# Schematic_Sheet_Arduino.net
KiCad netlist of a schematic drawn in Altium Designer
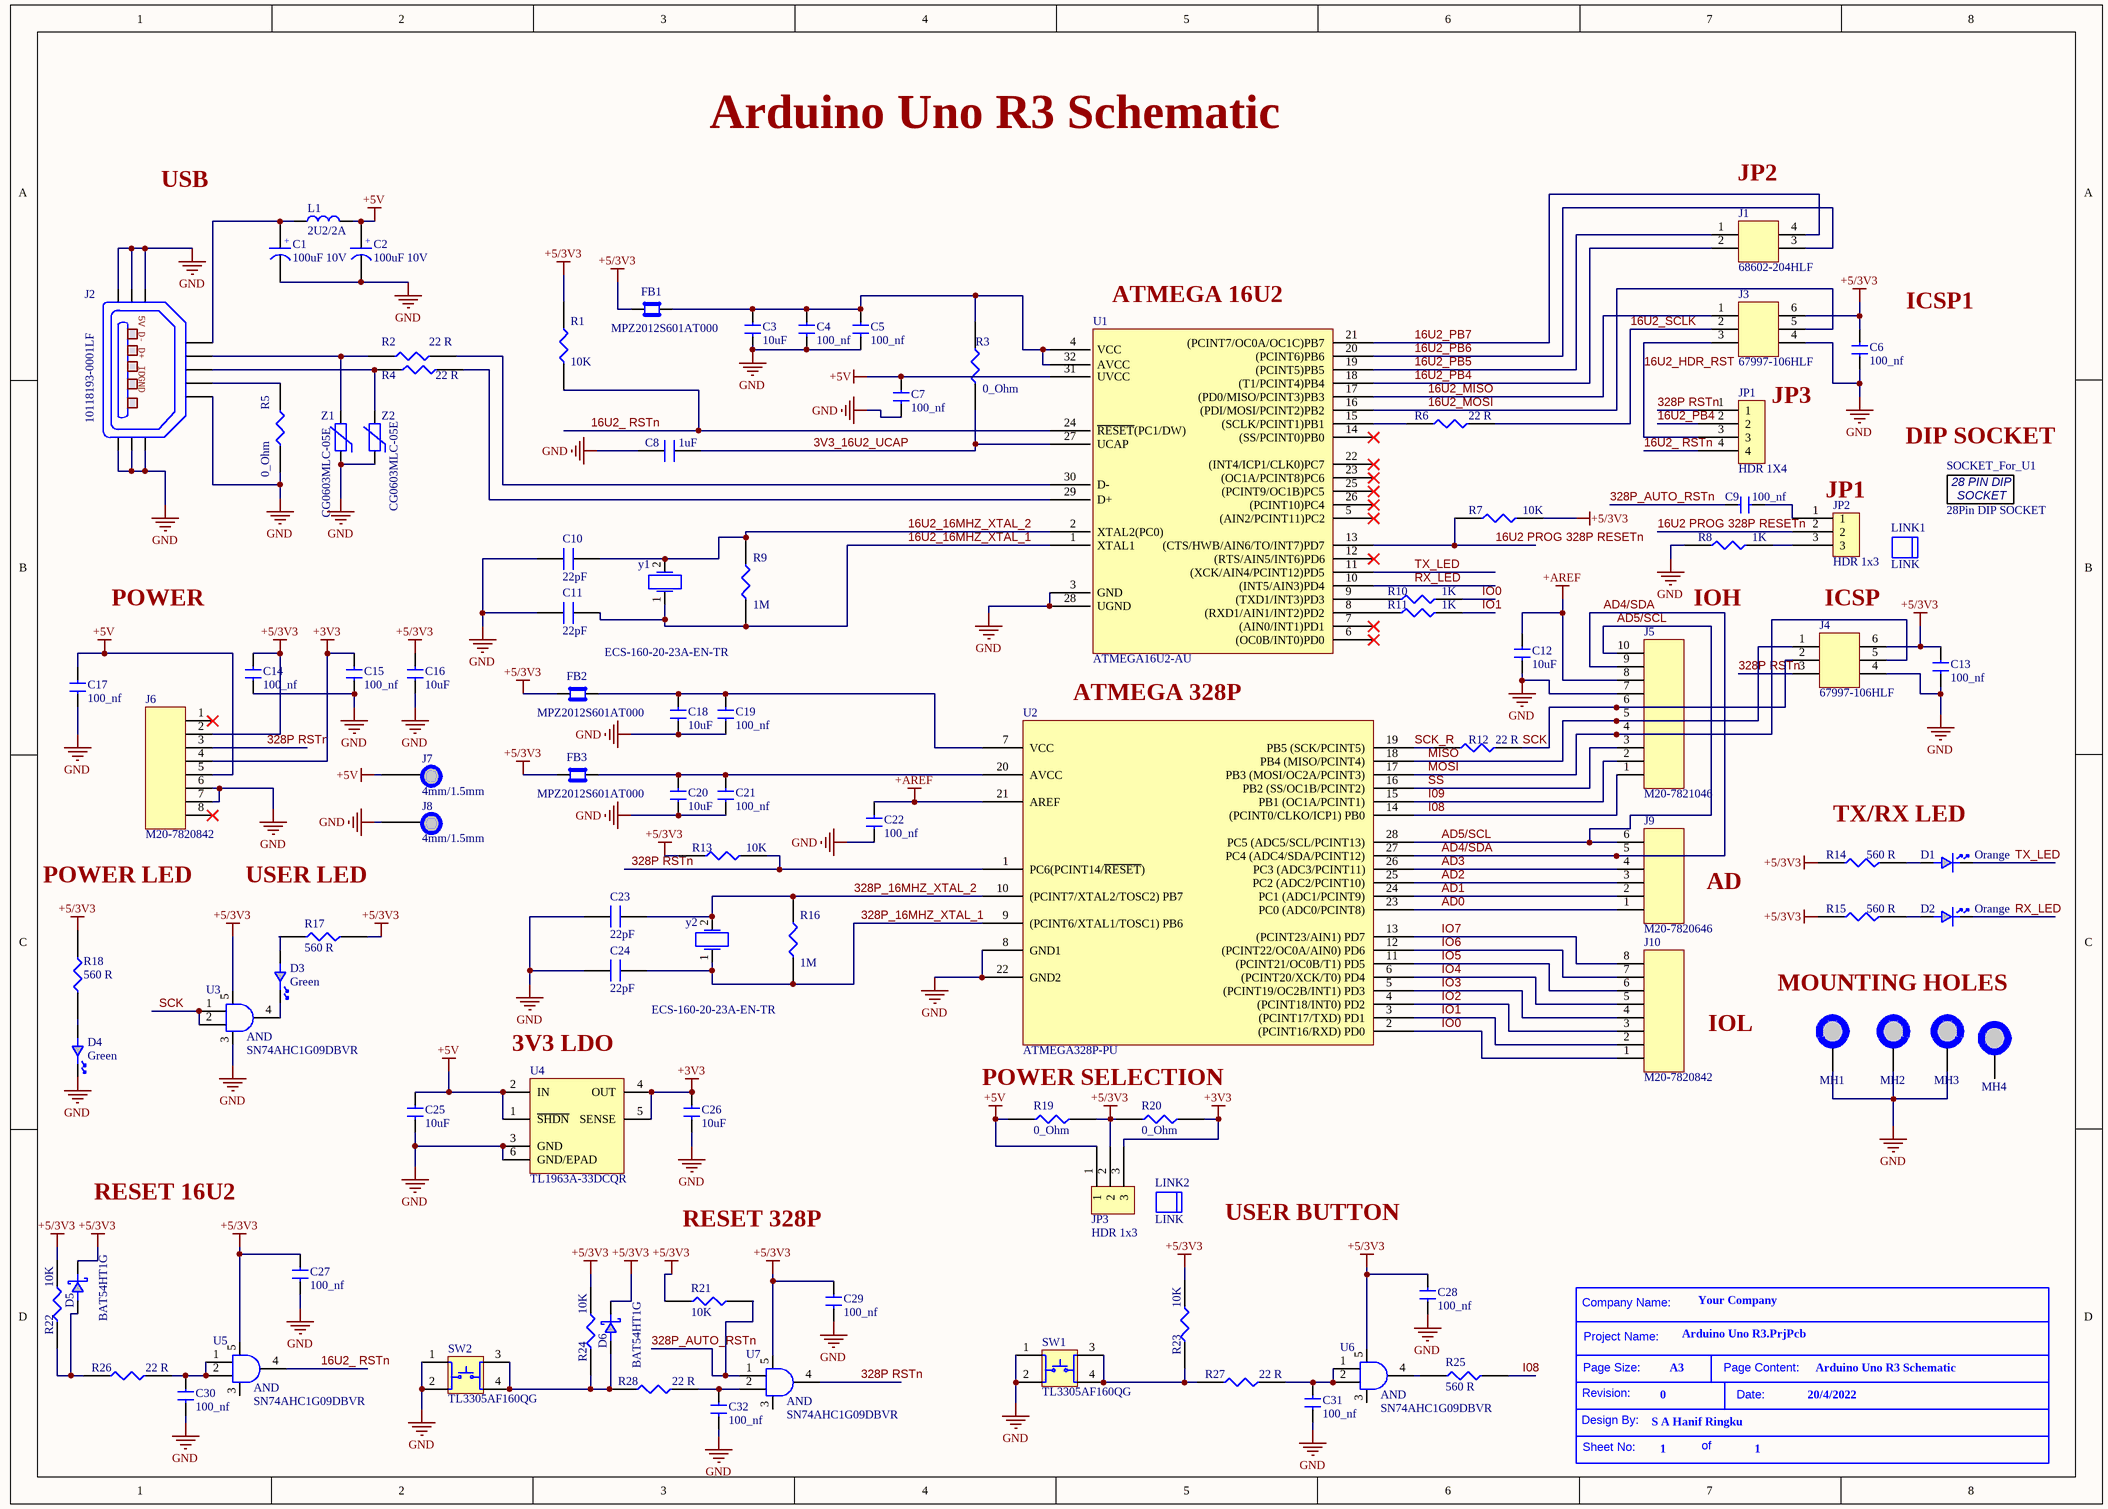
[diagram p0: Schematic Sheet Arduino .SchDoc]

(export (version "E")
  (design (tool "Eeschema 10.0.6"))
  (components
    (comp (ref "*")
      (value "Title_Block")
      (libsource (lib "Component Schematic Library V1") (part "Title_Block"))
    )
    (comp (ref "C1")
      (value "100uF 10V")
      (footprint "Cap_Alu_C_Size")
      (description "贴片铝电解电容 100uF ±20% 10V 1000hrs@85°C AEC_D5.0x5.4mm_SM")
      (fields
        (field (name "MANUFACTURER") "Panasonic")
        (field (name "MANUFACTURER PART NUMBER") "EEE-1AA101WR")
      )
      (libsource (lib "Component Schematic Library V1") (part "CAP_POLAR_100uf_10V"))
    )
    (comp (ref "C2")
      (value "100uF 10V")
      (footprint "Cap_Alu_C_Size")
      (description "贴片铝电解电容 100uF ±20% 10V 1000hrs@85°C AEC_D5.0x5.4mm_SM")
      (fields
        (field (name "MANUFACTURER") "Panasonic")
        (field (name "MANUFACTURER PART NUMBER") "EEE-1AA101WR")
      )
      (libsource (lib "Component Schematic Library V1") (part "CAP_POLAR_100uf_10V"))
    )
    (comp (ref "C3")
      (value "10uF")
      (footprint "CAP_0805")
      (fields
        (field (name "MANUFACTURER") "TDK")
        (field (name "MANUFACTURER PART NUMBER") "C2012X5R1C106M125AC")
        (field (name "TOLERANCE") "20%")
      )
      (libsource (lib "Component Schematic Library V1") (part "CAP_10uF_0805"))
    )
    (comp (ref "C4")
      (value "100_nf")
      (footprint "CAP_0805")
      (description "Cap Ceramic 0.1uF 50V X7R 10% SMD 0805 125°C Blister Plastic T/R")
      (fields
        (field (name "MANUFACTURER") "TDK")
        (field (name "MANUFACTURER PART NUMBER") "C2012X7R1H104K125AE")
      )
      (libsource (lib "Component Schematic Library V1") (part "CAP_ 0.1uf"))
    )
    (comp (ref "C5")
      (value "100_nf")
      (footprint "CAP_0805")
      (description "Cap Ceramic 0.1uF 50V X7R 10% SMD 0805 125°C Blister Plastic T/R")
      (fields
        (field (name "MANUFACTURER") "TDK")
        (field (name "MANUFACTURER PART NUMBER") "C2012X7R1H104K125AE")
      )
      (libsource (lib "Component Schematic Library V1") (part "CAP_ 0.1uf"))
    )
    (comp (ref "C6")
      (value "100_nf")
      (footprint "CAP_0805")
      (description "Cap Ceramic 0.1uF 50V X7R 10% SMD 0805 125°C Blister Plastic T/R")
      (fields
        (field (name "MANUFACTURER") "TDK")
        (field (name "MANUFACTURER PART NUMBER") "C2012X7R1H104K125AE")
      )
      (libsource (lib "Component Schematic Library V1") (part "CAP_ 0.1uf"))
    )
    (comp (ref "C7")
      (value "100_nf")
      (footprint "CAP_0805")
      (description "Cap Ceramic 0.1uF 50V X7R 10% SMD 0805 125°C Blister Plastic T/R")
      (fields
        (field (name "MANUFACTURER") "TDK")
        (field (name "MANUFACTURER PART NUMBER") "C2012X7R1H104K125AE")
      )
      (libsource (lib "Component Schematic Library V1") (part "CAP_ 0.1uf"))
    )
    (comp (ref "C8")
      (value "1uF")
      (footprint "CAP_0805")
      (fields
        (field (name "MANUFACTURER") "TDK")
        (field (name "MANUFACTURER PART NUMBER") "C2012X5R1E105K125AA")
        (field (name "TOLERANCE") "10%")
      )
      (libsource (lib "Component Schematic Library V1") (part "CAP_1uF_0805"))
    )
    (comp (ref "C9")
      (value "100_nf")
      (footprint "CAP_0805")
      (description "Cap Ceramic 0.1uF 50V X7R 10% SMD 0805 125°C Blister Plastic T/R")
      (fields
        (field (name "MANUFACTURER") "TDK")
        (field (name "MANUFACTURER PART NUMBER") "C2012X7R1H104K125AE")
      )
      (libsource (lib "Component Schematic Library V1") (part "CAP_ 0.1uf"))
    )
    (comp (ref "C10")
      (value "22pF")
      (footprint "CAP_0805")
      (description "Cap Ceramic 22pF 50V X7R 5% Pad SMD 0805 125C T/R")
      (fields
        (field (name "MANUFACTURER") "KEMET")
        (field (name "MANUFACTURER PART NUMBER") "C0805C220J5RAC7800")
      )
      (libsource (lib "Component Schematic Library V1") (part "CAP_22pF_0805"))
    )
    (comp (ref "C11")
      (value "22pF")
      (footprint "CAP_0805")
      (description "Cap Ceramic 22pF 50V X7R 5% Pad SMD 0805 125C T/R")
      (fields
        (field (name "MANUFACTURER") "KEMET")
        (field (name "MANUFACTURER PART NUMBER") "C0805C220J5RAC7800")
      )
      (libsource (lib "Component Schematic Library V1") (part "CAP_22pF_0805"))
    )
    (comp (ref "C12")
      (value "10uF")
      (footprint "CAP_0805")
      (fields
        (field (name "MANUFACTURER") "TDK")
        (field (name "MANUFACTURER PART NUMBER") "C2012X5R1C106M125AC")
        (field (name "TOLERANCE") "20%")
      )
      (libsource (lib "Component Schematic Library V1") (part "CAP_10uF_0805"))
    )
    (comp (ref "C13")
      (value "100_nf")
      (footprint "CAP_0805")
      (description "Cap Ceramic 0.1uF 50V X7R 10% SMD 0805 125°C Blister Plastic T/R")
      (fields
        (field (name "MANUFACTURER") "TDK")
        (field (name "MANUFACTURER PART NUMBER") "C2012X7R1H104K125AE")
      )
      (libsource (lib "Component Schematic Library V1") (part "CAP_ 0.1uf"))
    )
    (comp (ref "C14")
      (value "100_nf")
      (footprint "CAP_0805")
      (description "Cap Ceramic 0.1uF 50V X7R 10% SMD 0805 125°C Blister Plastic T/R")
      (fields
        (field (name "MANUFACTURER") "TDK")
        (field (name "MANUFACTURER PART NUMBER") "C2012X7R1H104K125AE")
      )
      (libsource (lib "Component Schematic Library V1") (part "CAP_ 0.1uf"))
    )
    (comp (ref "C15")
      (value "100_nf")
      (footprint "CAP_0805")
      (description "Cap Ceramic 0.1uF 50V X7R 10% SMD 0805 125°C Blister Plastic T/R")
      (fields
        (field (name "MANUFACTURER") "TDK")
        (field (name "MANUFACTURER PART NUMBER") "C2012X7R1H104K125AE")
      )
      (libsource (lib "Component Schematic Library V1") (part "CAP_ 0.1uf"))
    )
    (comp (ref "C16")
      (value "10uF")
      (footprint "CAP_0805")
      (fields
        (field (name "MANUFACTURER") "TDK")
        (field (name "MANUFACTURER PART NUMBER") "C2012X5R1C106M125AC")
        (field (name "TOLERANCE") "20%")
      )
      (libsource (lib "Component Schematic Library V1") (part "CAP_10uF_0805"))
    )
    (comp (ref "C17")
      (value "100_nf")
      (footprint "CAP_0805")
      (description "Cap Ceramic 0.1uF 50V X7R 10% SMD 0805 125°C Blister Plastic T/R")
      (fields
        (field (name "MANUFACTURER") "TDK")
        (field (name "MANUFACTURER PART NUMBER") "C2012X7R1H104K125AE")
      )
      (libsource (lib "Component Schematic Library V1") (part "CAP_ 0.1uf"))
    )
    (comp (ref "C18")
      (value "10uF")
      (footprint "CAP_0805")
      (fields
        (field (name "MANUFACTURER") "TDK")
        (field (name "MANUFACTURER PART NUMBER") "C2012X5R1C106M125AC")
        (field (name "TOLERANCE") "20%")
      )
      (libsource (lib "Component Schematic Library V1") (part "CAP_10uF_0805"))
    )
    (comp (ref "C19")
      (value "100_nf")
      (footprint "CAP_0805")
      (description "Cap Ceramic 0.1uF 50V X7R 10% SMD 0805 125°C Blister Plastic T/R")
      (fields
        (field (name "MANUFACTURER") "TDK")
        (field (name "MANUFACTURER PART NUMBER") "C2012X7R1H104K125AE")
      )
      (libsource (lib "Component Schematic Library V1") (part "CAP_ 0.1uf"))
    )
    (comp (ref "C20")
      (value "10uF")
      (footprint "CAP_0805")
      (fields
        (field (name "MANUFACTURER") "TDK")
        (field (name "MANUFACTURER PART NUMBER") "C2012X5R1C106M125AC")
        (field (name "TOLERANCE") "20%")
      )
      (libsource (lib "Component Schematic Library V1") (part "CAP_10uF_0805"))
    )
    (comp (ref "C21")
      (value "100_nf")
      (footprint "CAP_0805")
      (description "Cap Ceramic 0.1uF 50V X7R 10% SMD 0805 125°C Blister Plastic T/R")
      (fields
        (field (name "MANUFACTURER") "TDK")
        (field (name "MANUFACTURER PART NUMBER") "C2012X7R1H104K125AE")
      )
      (libsource (lib "Component Schematic Library V1") (part "CAP_ 0.1uf"))
    )
    (comp (ref "C22")
      (value "100_nf")
      (footprint "CAP_0805")
      (description "Cap Ceramic 0.1uF 50V X7R 10% SMD 0805 125°C Blister Plastic T/R")
      (fields
        (field (name "MANUFACTURER") "TDK")
        (field (name "MANUFACTURER PART NUMBER") "C2012X7R1H104K125AE")
      )
      (libsource (lib "Component Schematic Library V1") (part "CAP_ 0.1uf"))
    )
    (comp (ref "C23")
      (value "22pF")
      (footprint "CAP_0805")
      (description "Cap Ceramic 22pF 50V X7R 5% Pad SMD 0805 125C T/R")
      (fields
        (field (name "MANUFACTURER") "KEMET")
        (field (name "MANUFACTURER PART NUMBER") "C0805C220J5RAC7800")
      )
      (libsource (lib "Component Schematic Library V1") (part "CAP_22pF_0805"))
    )
    (comp (ref "C24")
      (value "22pF")
      (footprint "CAP_0805")
      (description "Cap Ceramic 22pF 50V X7R 5% Pad SMD 0805 125C T/R")
      (fields
        (field (name "MANUFACTURER") "KEMET")
        (field (name "MANUFACTURER PART NUMBER") "C0805C220J5RAC7800")
      )
      (libsource (lib "Component Schematic Library V1") (part "CAP_22pF_0805"))
    )
    (comp (ref "C25")
      (value "10uF")
      (footprint "CAP_0805")
      (fields
        (field (name "MANUFACTURER") "TDK")
        (field (name "MANUFACTURER PART NUMBER") "C2012X5R1C106M125AC")
        (field (name "TOLERANCE") "20%")
      )
      (libsource (lib "Component Schematic Library V1") (part "CAP_10uF_0805"))
    )
    (comp (ref "C26")
      (value "10uF")
      (footprint "CAP_0805")
      (fields
        (field (name "MANUFACTURER") "TDK")
        (field (name "MANUFACTURER PART NUMBER") "C2012X5R1C106M125AC")
        (field (name "TOLERANCE") "20%")
      )
      (libsource (lib "Component Schematic Library V1") (part "CAP_10uF_0805"))
    )
    (comp (ref "C27")
      (value "100_nf")
      (footprint "CAP_0805")
      (description "Cap Ceramic 0.1uF 50V X7R 10% SMD 0805 125°C Blister Plastic T/R")
      (fields
        (field (name "MANUFACTURER") "TDK")
        (field (name "MANUFACTURER PART NUMBER") "C2012X7R1H104K125AE")
      )
      (libsource (lib "Component Schematic Library V1") (part "CAP_ 0.1uf"))
    )
    (comp (ref "C28")
      (value "100_nf")
      (footprint "CAP_0805")
      (description "Cap Ceramic 0.1uF 50V X7R 10% SMD 0805 125°C Blister Plastic T/R")
      (fields
        (field (name "MANUFACTURER") "TDK")
        (field (name "MANUFACTURER PART NUMBER") "C2012X7R1H104K125AE")
      )
      (libsource (lib "Component Schematic Library V1") (part "CAP_ 0.1uf"))
    )
    (comp (ref "C29")
      (value "100_nf")
      (footprint "CAP_0805")
      (description "Cap Ceramic 0.1uF 50V X7R 10% SMD 0805 125°C Blister Plastic T/R")
      (fields
        (field (name "MANUFACTURER") "TDK")
        (field (name "MANUFACTURER PART NUMBER") "C2012X7R1H104K125AE")
      )
      (libsource (lib "Component Schematic Library V1") (part "CAP_ 0.1uf"))
    )
    (comp (ref "C30")
      (value "100_nf")
      (footprint "CAP_0805")
      (description "Cap Ceramic 0.1uF 50V X7R 10% SMD 0805 125°C Blister Plastic T/R")
      (fields
        (field (name "MANUFACTURER") "TDK")
        (field (name "MANUFACTURER PART NUMBER") "C2012X7R1H104K125AE")
      )
      (libsource (lib "Component Schematic Library V1") (part "CAP_ 0.1uf"))
    )
    (comp (ref "C31")
      (value "100_nf")
      (footprint "CAP_0805")
      (description "Cap Ceramic 0.1uF 50V X7R 10% SMD 0805 125°C Blister Plastic T/R")
      (fields
        (field (name "MANUFACTURER") "TDK")
        (field (name "MANUFACTURER PART NUMBER") "C2012X7R1H104K125AE")
      )
      (libsource (lib "Component Schematic Library V1") (part "CAP_ 0.1uf"))
    )
    (comp (ref "C32")
      (value "100_nf")
      (footprint "CAP_0805")
      (description "Cap Ceramic 0.1uF 50V X7R 10% SMD 0805 125°C Blister Plastic T/R")
      (fields
        (field (name "MANUFACTURER") "TDK")
        (field (name "MANUFACTURER PART NUMBER") "C2012X7R1H104K125AE")
      )
      (libsource (lib "Component Schematic Library V1") (part "CAP_ 0.1uf"))
    )
    (comp (ref "D1")
      (value "Orange")
      (footprint "LED 0603")
      (description "Smartled Orange Lc")
      (fields
        (field (name "MANUFACTURER") "Osram Opto")
        (field (name "MANUFACTURER PART NUMBER") "LOL29K-H2K1-24-Z")
      )
      (libsource (lib "Component Schematic Library V1") (part "LED_Orange"))
    )
    (comp (ref "D2")
      (value "Orange")
      (footprint "LED 0603")
      (description "Smartled Orange Lc")
      (fields
        (field (name "MANUFACTURER") "Osram Opto")
        (field (name "MANUFACTURER PART NUMBER") "LOL29K-H2K1-24-Z")
      )
      (libsource (lib "Component Schematic Library V1") (part "LED_Orange"))
    )
    (comp (ref "D3")
      (value "Green")
      (footprint "LED 0603")
      (description "LED Single Chip Green 570nm 20mA 2-Pin 0603 T/R")
      (fields
        (field (name "MANUFACTURER") "Osram Opto")
        (field (name "MANUFACTURER PART NUMBER") "LGL29K-G2J1-24-Z")
      )
      (libsource (lib "Component Schematic Library V1") (part "LED_Green"))
    )
    (comp (ref "D4")
      (value "Green")
      (footprint "LED 0603")
      (description "LED Single Chip Green 570nm 20mA 2-Pin 0603 T/R")
      (fields
        (field (name "MANUFACTURER") "Osram Opto")
        (field (name "MANUFACTURER PART NUMBER") "LGL29K-G2J1-24-Z")
      )
      (libsource (lib "Component Schematic Library V1") (part "LED_Green"))
    )
    (comp (ref "D5")
      (value "BAT54HT1G")
      (footprint "SOD323")
      (description "VR=30V IF=200mA 10pF P=200mW")
      (fields (field (name "MANUFACTURER") "ON Semiconductor / Fairchild"))
      (libsource (lib "Component Schematic Library V1") (part "Shottky_Diode"))
    )
    (comp (ref "D6")
      (value "BAT54HT1G")
      (footprint "SOD323")
      (description "VR=30V IF=200mA 10pF P=200mW")
      (fields (field (name "MANUFACTURER") "ON Semiconductor / Fairchild"))
      (libsource (lib "Component Schematic Library V1") (part "Shottky_Diode"))
    )
    (comp (ref "FB1")
      (value "MPZ2012S601AT000")
      (footprint "CAP_0805")
      (description "0805 600Ω ±25% DCR=0.1Ω 2A")
      (fields (field (name "MANUFACTURER") "TDK"))
      (libsource (lib "Component Schematic Library V1") (part "Ferrite Bit"))
    )
    (comp (ref "FB2")
      (value "MPZ2012S601AT000")
      (footprint "CAP_0805")
      (description "0805 600Ω ±25% DCR=0.1Ω 2A")
      (fields (field (name "MANUFACTURER") "TDK"))
      (libsource (lib "Component Schematic Library V1") (part "Ferrite Bit"))
    )
    (comp (ref "FB3")
      (value "MPZ2012S601AT000")
      (footprint "CAP_0805")
      (description "0805 600Ω ±25% DCR=0.1Ω 2A")
      (fields (field (name "MANUFACTURER") "TDK"))
      (libsource (lib "Component Schematic Library V1") (part "Ferrite Bit"))
    )
    (comp (ref "J1")
      (value "68602-204HLF")
      (footprint "Male_HDR_2X2_2.54")
      (description "Conn Unshrouded Header HDR 4 POS 2.54mm Solder ST Top Entry Thru-Hole BergStik® Bulk")
      (fields (field (name "MANUFACTURER") "Amphenol ICC / FCI"))
      (libsource (lib "Component Schematic Library V1") (part "Male_HDR_2X2_2.54mm_Pitch"))
    )
    (comp (ref "J2")
      (value "10118193-0001LF")
      (footprint "USB")
      (description "FCI Right Angle Surface Mount Mount Female USB Connector; 100 V ac; 1.8A")
      (fields (field (name "MANUFACTURER") "Amphenol ICC / FCI"))
      (libsource (lib "Component Schematic Library V1") (part "Micro_USB"))
    )
    (comp (ref "J3")
      (value "67997-106HLF")
      (footprint "MALE_HDR_3X2_2.54mm")
      (description "Conn Unshrouded Header HDR 6 POS 2.54mm Solder ST Top Entry Thru-Hole BergStik® Bulk")
      (fields (field (name "MANUFACTURER") "Amphenol ICC / FCI"))
      (libsource (lib "Component Schematic Library V1") (part "Male_HDR_3X2_2.54mm_Pitch"))
    )
    (comp (ref "J4")
      (value "67997-106HLF")
      (footprint "MALE_HDR_3X2_2.54mm")
      (description "Conn Unshrouded Header HDR 6 POS 2.54mm Solder ST Top Entry Thru-Hole BergStik® Bulk")
      (fields (field (name "MANUFACTURER") "Amphenol ICC / FCI"))
      (libsource (lib "Component Schematic Library V1") (part "Male_HDR_3X2_2.54mm_Pitch"))
    )
    (comp (ref "J5")
      (value "M20-7821046")
      (footprint "Female_HDR_10\\X1_2.54mm_Pitch")
      (description "2.54mm (0.1\") Pitch SIL Vertical PC Tail Socket Assembly, tin, 10 contacts")
      (fields (field (name "MANUFACTURER") "Harwin"))
      (libsource (lib "Component Schematic Library V1") (part "Female_Header 10X1_Pins_2.54_mm_Pitch"))
    )
    (comp (ref "J6")
      (value "M20-7820842")
      (footprint "Female_HDR_8\\X1_2.54mm_Pitch")
      (description "2.54mm (0.1\") Pitch SIL Vertical PC Tail Socket Assembly, selective gold + tin, 8 contacts")
      (fields (field (name "MANUFACTURER") "Harwin"))
      (libsource (lib "") (part "Female_Header 8X1_Pins_2.54_mm_Pitch_1"))
    )
    (comp (ref "J7")
      (value "4mm/1.5mm")
      (footprint "PAD_WITH_HOLE_4MM/1.5MM")
      (description "PAD With Whole 4mm/1.5mm")
      (libsource (lib "Component Schematic Library V1") (part "PAD_WITH_HOLE_4mm_5mm"))
    )
    (comp (ref "J8")
      (value "4mm/1.5mm")
      (footprint "PAD_WITH_HOLE_4MM/1.5MM")
      (description "PAD With Whole 4mm/1.5mm")
      (libsource (lib "Component Schematic Library V1") (part "PAD_WITH_HOLE_4mm_5mm"))
    )
    (comp (ref "J9")
      (value "M20-7820646")
      (footprint "Female_HDR_6X1_2.54mm_Pitch")
      (description "2.54mm (0.1\") Pitch SIL Vertical PC Tail Socket Assembly, tin, 6 contacts")
      (fields (field (name "MANUFACTURER") "Harwin"))
      (libsource (lib "Component Schematic Library V1") (part "Female_Header 6X1_Pins_2.54_mm_Pitch"))
    )
    (comp (ref "J10")
      (value "M20-7820842")
      (footprint "Female_HDR_8\\X1_2.54mm_Pitch")
      (description "2.54mm (0.1\") Pitch SIL Vertical PC Tail Socket Assembly, selective gold + tin, 8 contacts")
      (fields (field (name "MANUFACTURER") "Harwin"))
      (libsource (lib "Component Schematic Library V1") (part "Female_Header 8X1_Pins_2.54_mm_Pitch"))
    )
    (comp (ref "JP1")
      (value "HDR 1X4")
      (footprint "HDR 1X4")
      (description "Conn Unshrouded Header HDR 4 POS 2.54mm Solder ST Thru-Hole Bag")
      (fields
        (field (name "MANUFACTURER") "Amphenol ICC")
        (field (name "MANUFACTURER PART NUMBER") "68001-204HLF")
      )
      (libsource (lib "Component Schematic Library V1") (part "MALE_HDR_4X1_Unschrouded"))
    )
    (comp (ref "JP2")
      (value "HDR 1x3")
      (footprint "HDR 1x3")
      (description "Conn Unshrouded Header HDR 3 POS 2.54mm Solder ST Top Entry Thru-Hole BergStik® Bulk")
      (fields
        (field (name "MANUFACTURER") "Amphenol ICC / FCI")
        (field (name "MANUFACTURER PART NUMBER") "68797-403HLF")
      )
      (libsource (lib "Component Schematic Library V1") (part "Male_HDR_1X3_Unschrouded"))
    )
    (comp (ref "JP3")
      (value "HDR 1x3")
      (footprint "HDR 1x3")
      (description "Conn Unshrouded Header HDR 3 POS 2.54mm Solder ST Top Entry Thru-Hole BergStik® Bulk")
      (fields
        (field (name "MANUFACTURER") "Amphenol ICC / FCI")
        (field (name "MANUFACTURER PART NUMBER") "68797-403HLF")
      )
      (libsource (lib "") (part "Male_HDR_1X3_Unschrouded_1"))
    )
    (comp (ref "L1")
      (value "2U2/2A")
      (footprint "C1210_Inductor")
      (description "Inductor RF Chip Wirewound 2.2uH 20% 100KHz 1.13A 0.104Ohm DCR 1210 T/R")
      (fields
        (field (name "MANUFACTURER") "KEMET")
        (field (name "MANUFACTURER PART NUMBER") "L1210R2R2MDWIT")
      )
      (libsource (lib "Component Schematic Library V1") (part "Inductor_2.2uH"))
    )
    (comp (ref "LINK1")
      (value "LINK")
      (description "2 Position 2.54 mm Centerline Single Circuit Open Top Jumper")
      (fields
        (field (name "MANUFACTURER") "Sullins")
        (field (name "MANUFACTURER PART NUMBER") "QPC02SXGN-RC")
      )
      (libsource (lib "Component Schematic Library V1") (part "Connector_Open_Top_Jumper"))
    )
    (comp (ref "LINK2")
      (value "LINK")
      (description "2 Position 2.54 mm Centerline Single Circuit Open Top Jumper")
      (fields
        (field (name "MANUFACTURER") "Sullins")
        (field (name "MANUFACTURER PART NUMBER") "QPC02SXGN-RC")
      )
      (libsource (lib "Component Schematic Library V1") (part "Connector_Open_Top_Jumper"))
    )
    (comp (ref "MH1")
      (value "MH_7.4_MHC_3.2")
      (footprint "MH_7.4 and 3.2 mm")
      (description "Mounting Hole 7.4 mm Diameter and 3.2 mm drill")
      (libsource (lib "Component Schematic Library V1") (part "MH 7.4 /3.2"))
    )
    (comp (ref "MH2")
      (value "MH_7.4_MHC_3.2")
      (footprint "MH_7.4 and 3.2 mm")
      (description "Mounting Hole 7.4 mm Diameter and 3.2 mm drill")
      (libsource (lib "Component Schematic Library V1") (part "MH 7.4 /3.2"))
    )
    (comp (ref "MH3")
      (value "MH_7.4_MHC_3.2")
      (footprint "MH_7.4 and 3.2 mm")
      (description "Mounting Hole 7.4 mm Diameter and 3.2 mm drill")
      (libsource (lib "Component Schematic Library V1") (part "MH 7.4 /3.2"))
    )
    (comp (ref "MH4")
      (value "Mountain Hole Non Plated")
      (footprint "MH_non_plated")
      (description "Mountain Hole 7.4 mm diameter no coper drill 3.2 mm")
      (libsource (lib "Component Schematic Library V1") (part "MH Non Plated 7.4X3.2"))
    )
    (comp (ref "R1")
      (value "10K")
      (footprint "R_0805")
      (description "贴片电阻 10000Ω ± 1.00% 0.125W ± 100ppm/℃ 0805")
      (fields
        (field (name "MANUFACTURER") "Yageo")
        (field (name "MANUFACTURER PART NUMBER") "RC0805FR-0710KL")
      )
      (libsource (lib "Component Schematic Library V1") (part "RES_10_K_0805"))
    )
    (comp (ref "R2")
      (value "22 R")
      (footprint "R_0805")
      (description "贴片电阻 22Ω ± 1.00% 0.125W ± 100ppm/℃ 0805")
      (fields
        (field (name "MANUFACTURER") "Yageo")
        (field (name "MANUFACTURER PART NUMBER") "RC0805FR-0722RL")
      )
      (libsource (lib "Component Schematic Library V1") (part "RES_22_Ohm_0805"))
    )
    (comp (ref "R3")
      (value "0_Ohm")
      (footprint "R_0805")
      (description "贴片电阻 0Ω ±5% 1/8W 0805")
      (fields
        (field (name "MANUFACTURER") "Yageo")
        (field (name "MANUFACTURER PART NUMBER") "RC0805JR-070RL")
      )
      (libsource (lib "Component Schematic Library V1") (part "RES_0_Ohm_0805"))
    )
    (comp (ref "R4")
      (value "22 R")
      (footprint "R_0805")
      (description "贴片电阻 22Ω ± 1.00% 0.125W ± 100ppm/℃ 0805")
      (fields
        (field (name "MANUFACTURER") "Yageo")
        (field (name "MANUFACTURER PART NUMBER") "RC0805FR-0722RL")
      )
      (libsource (lib "Component Schematic Library V1") (part "RES_22_Ohm_0805"))
    )
    (comp (ref "R5")
      (value "0_Ohm")
      (footprint "R_0805")
      (description "贴片电阻 0Ω ±5% 1/8W 0805")
      (fields
        (field (name "MANUFACTURER") "Yageo")
        (field (name "MANUFACTURER PART NUMBER") "RC0805JR-070RL")
      )
      (libsource (lib "Component Schematic Library V1") (part "RES_0_Ohm_0805"))
    )
    (comp (ref "R6")
      (value "22 R")
      (footprint "R_0805")
      (description "贴片电阻 22Ω ± 1.00% 0.125W ± 100ppm/℃ 0805")
      (fields
        (field (name "MANUFACTURER") "Yageo")
        (field (name "MANUFACTURER PART NUMBER") "RC0805FR-0722RL")
      )
      (libsource (lib "Component Schematic Library V1") (part "RES_22_Ohm_0805"))
    )
    (comp (ref "R7")
      (value "10K")
      (footprint "R_0805")
      (description "贴片电阻 10000Ω ± 1.00% 0.125W ± 100ppm/℃ 0805")
      (fields
        (field (name "MANUFACTURER") "Yageo")
        (field (name "MANUFACTURER PART NUMBER") "RC0805FR-0710KL")
      )
      (libsource (lib "Component Schematic Library V1") (part "RES_10_K_0805"))
    )
    (comp (ref "R8")
      (value "1K")
      (footprint "R_0805")
      (description "贴片电阻 1000Ω ± 1.00% 0.125W ± 100ppm/℃ 0805")
      (fields
        (field (name "MANUFACTURER") "Yageo")
        (field (name "MANUFACTURER PART NUMBER") "RC0805FR-071KL")
      )
      (libsource (lib "Component Schematic Library V1") (part "RES_1_K_0805"))
    )
    (comp (ref "R9")
      (value "1M")
      (footprint "R_0805")
      (description "贴片电阻 1000000Ω ± 1.00% 0.125W ± 100ppm/℃ 0805")
      (fields
        (field (name "MANUFACTURER") "Yageo")
        (field (name "MANUFACTURER PART NUMBER") "RC0805FR-071ML")
      )
      (libsource (lib "Component Schematic Library V1") (part "RES_1M_0805"))
    )
    (comp (ref "R10")
      (value "1K")
      (footprint "R_0805")
      (description "贴片电阻 1000Ω ± 1.00% 0.125W ± 100ppm/℃ 0805")
      (fields
        (field (name "MANUFACTURER") "Yageo")
        (field (name "MANUFACTURER PART NUMBER") "RC0805FR-071KL")
      )
      (libsource (lib "Component Schematic Library V1") (part "RES_1_K_0805"))
    )
    (comp (ref "R11")
      (value "1K")
      (footprint "R_0805")
      (description "贴片电阻 1000Ω ± 1.00% 0.125W ± 100ppm/℃ 0805")
      (fields
        (field (name "MANUFACTURER") "Yageo")
        (field (name "MANUFACTURER PART NUMBER") "RC0805FR-071KL")
      )
      (libsource (lib "Component Schematic Library V1") (part "RES_1_K_0805"))
    )
    (comp (ref "R12")
      (value "22 R")
      (footprint "R_0805")
      (description "贴片电阻 22Ω ± 1.00% 0.125W ± 100ppm/℃ 0805")
      (fields
        (field (name "MANUFACTURER") "Yageo")
        (field (name "MANUFACTURER PART NUMBER") "RC0805FR-0722RL")
      )
      (libsource (lib "Component Schematic Library V1") (part "RES_22_Ohm_0805"))
    )
    (comp (ref "R13")
      (value "10K")
      (footprint "R_0805")
      (description "贴片电阻 10000Ω ± 1.00% 0.125W ± 100ppm/℃ 0805")
      (fields
        (field (name "MANUFACTURER") "Yageo")
        (field (name "MANUFACTURER PART NUMBER") "RC0805FR-0710KL")
      )
      (libsource (lib "Component Schematic Library V1") (part "RES_10_K_0805"))
    )
    (comp (ref "R14")
      (value "560 R")
      (footprint "R_0805")
      (description "贴片电阻 560Ω ± 1.00% 0.125W ± 100ppm/℃ 0805")
      (fields
        (field (name "MANUFACTURER") "Yageo")
        (field (name "MANUFACTURER PART NUMBER") "RC0805FR-07560RL")
      )
      (libsource (lib "Component Schematic Library V1") (part "RES_560_Ohm_0805"))
    )
    (comp (ref "R15")
      (value "560 R")
      (footprint "R_0805")
      (description "贴片电阻 560Ω ± 1.00% 0.125W ± 100ppm/℃ 0805")
      (fields
        (field (name "MANUFACTURER") "Yageo")
        (field (name "MANUFACTURER PART NUMBER") "RC0805FR-07560RL")
      )
      (libsource (lib "Component Schematic Library V1") (part "RES_560_Ohm_0805"))
    )
    (comp (ref "R16")
      (value "1M")
      (footprint "R_0805")
      (description "贴片电阻 1000000Ω ± 1.00% 0.125W ± 100ppm/℃ 0805")
      (fields
        (field (name "MANUFACTURER") "Yageo")
        (field (name "MANUFACTURER PART NUMBER") "RC0805FR-071ML")
      )
      (libsource (lib "Component Schematic Library V1") (part "RES_1M_0805"))
    )
    (comp (ref "R17")
      (value "560 R")
      (footprint "R_0805")
      (description "贴片电阻 560Ω ± 1.00% 0.125W ± 100ppm/℃ 0805")
      (fields
        (field (name "MANUFACTURER") "Yageo")
        (field (name "MANUFACTURER PART NUMBER") "RC0805FR-07560RL")
      )
      (libsource (lib "Component Schematic Library V1") (part "RES_560_Ohm_0805"))
    )
    (comp (ref "R18")
      (value "560 R")
      (footprint "R_0805")
      (description "贴片电阻 560Ω ± 1.00% 0.125W ± 100ppm/℃ 0805")
      (fields
        (field (name "MANUFACTURER") "Yageo")
        (field (name "MANUFACTURER PART NUMBER") "RC0805FR-07560RL")
      )
      (libsource (lib "Component Schematic Library V1") (part "RES_560_Ohm_0805"))
    )
    (comp (ref "R19")
      (value "0_Ohm")
      (footprint "R_0805")
      (description "贴片电阻 0Ω ±5% 1/8W 0805")
      (fields
        (field (name "MANUFACTURER") "Yageo")
        (field (name "MANUFACTURER PART NUMBER") "RC0805JR-070RL")
      )
      (libsource (lib "Component Schematic Library V1") (part "RES_0_Ohm_0805"))
    )
    (comp (ref "R20")
      (value "0_Ohm")
      (footprint "R_0805")
      (description "贴片电阻 0Ω ±5% 1/8W 0805")
      (fields
        (field (name "MANUFACTURER") "Yageo")
        (field (name "MANUFACTURER PART NUMBER") "RC0805JR-070RL")
      )
      (libsource (lib "Component Schematic Library V1") (part "RES_0_Ohm_0805"))
    )
    (comp (ref "R21")
      (value "10K")
      (footprint "R_0805")
      (description "贴片电阻 10000Ω ± 1.00% 0.125W ± 100ppm/℃ 0805")
      (fields
        (field (name "MANUFACTURER") "Yageo")
        (field (name "MANUFACTURER PART NUMBER") "RC0805FR-0710KL")
      )
      (libsource (lib "Component Schematic Library V1") (part "RES_10_K_0805"))
    )
    (comp (ref "R22")
      (value "10K")
      (footprint "R_0805")
      (description "贴片电阻 10000Ω ± 1.00% 0.125W ± 100ppm/℃ 0805")
      (fields
        (field (name "MANUFACTURER") "Yageo")
        (field (name "MANUFACTURER PART NUMBER") "RC0805FR-0710KL")
      )
      (libsource (lib "Component Schematic Library V1") (part "RES_10_K_0805"))
    )
    (comp (ref "R23")
      (value "10K")
      (footprint "R_0805")
      (description "贴片电阻 10000Ω ± 1.00% 0.125W ± 100ppm/℃ 0805")
      (fields
        (field (name "MANUFACTURER") "Yageo")
        (field (name "MANUFACTURER PART NUMBER") "RC0805FR-0710KL")
      )
      (libsource (lib "Component Schematic Library V1") (part "RES_10_K_0805"))
    )
    (comp (ref "R24")
      (value "10K")
      (footprint "R_0805")
      (description "贴片电阻 10000Ω ± 1.00% 0.125W ± 100ppm/℃ 0805")
      (fields
        (field (name "MANUFACTURER") "Yageo")
        (field (name "MANUFACTURER PART NUMBER") "RC0805FR-0710KL")
      )
      (libsource (lib "Component Schematic Library V1") (part "RES_10_K_0805"))
    )
    (comp (ref "R25")
      (value "560 R")
      (footprint "R_0805")
      (description "贴片电阻 560Ω ± 1.00% 0.125W ± 100ppm/℃ 0805")
      (fields
        (field (name "MANUFACTURER") "Yageo")
        (field (name "MANUFACTURER PART NUMBER") "RC0805FR-07560RL")
      )
      (libsource (lib "Component Schematic Library V1") (part "RES_560_Ohm_0805"))
    )
    (comp (ref "R26")
      (value "22 R")
      (footprint "R_0805")
      (description "贴片电阻 22Ω ± 1.00% 0.125W ± 100ppm/℃ 0805")
      (fields
        (field (name "MANUFACTURER") "Yageo")
        (field (name "MANUFACTURER PART NUMBER") "RC0805FR-0722RL")
      )
      (libsource (lib "Component Schematic Library V1") (part "RES_22_Ohm_0805"))
    )
    (comp (ref "R27")
      (value "22 R")
      (footprint "R_0805")
      (description "贴片电阻 22Ω ± 1.00% 0.125W ± 100ppm/℃ 0805")
      (fields
        (field (name "MANUFACTURER") "Yageo")
        (field (name "MANUFACTURER PART NUMBER") "RC0805FR-0722RL")
      )
      (libsource (lib "Component Schematic Library V1") (part "RES_22_Ohm_0805"))
    )
    (comp (ref "R28")
      (value "22 R")
      (footprint "R_0805")
      (description "贴片电阻 22Ω ± 1.00% 0.125W ± 100ppm/℃ 0805")
      (fields
        (field (name "MANUFACTURER") "Yageo")
        (field (name "MANUFACTURER PART NUMBER") "RC0805FR-0722RL")
      )
      (libsource (lib "Component Schematic Library V1") (part "RES_22_Ohm_0805"))
    )
    (comp (ref "SOCKET_For_U1")
      (value "28Pin DIP SOCKET")
      (footprint "28 DIP_7.62mm_SOCKET")
      (description "Socket DIP 28Cnts DualWipe 0.3InSpc. PhosphorBronze Nickel KinkedTail 4800Series")
      (fields (field (name "MANUFACTURER") "3M") (field (name "MANUFACTURER PART NUMBER") "4828-3004-CP"))
      (libsource (lib "Component Schematic Library V1") (part "28_PIN_DIP_Socket"))
    )
    (comp (ref "SW1")
      (value "TL3305AF160QG")
      (footprint "SW_PB_SMD")
      (description "TL3305A Series SPST 12 V 4.5 x 4.5 mm 160 gf Top Actuated SMT Tactile Switch")
      (fields (field (name "MANUFACTURER") "E-Switch"))
      (libsource (lib "Component Schematic Library V1") (part "SW_PB"))
    )
    (comp (ref "SW2")
      (value "TL3305AF160QG")
      (footprint "SW_PB_SMD")
      (description "TL3305A Series SPST 12 V 4.5 x 4.5 mm 160 gf Top Actuated SMT Tactile Switch")
      (fields (field (name "MANUFACTURER") "E-Switch"))
      (libsource (lib "Component Schematic Library V1") (part "SW_PB"))
    )
    (comp (ref "U1")
      (value "ATMEGA16U2-AU")
      (footprint "TQFP32")
      (description "8-bit AVR MCU, 16 KB, 512 Bytes, 16 MHz, 2.7 to 5.5V, TQFP-32, RoHS")
      (fields (field (name "MANUFACTURER") "Microchip"))
      (libsource (lib "Component Schematic Library V1") (part "ATMEGA16U2-AU_Microcontroller"))
    )
    (comp (ref "U2")
      (value "ATMEGA328P-PU")
      (footprint "Atmega_328P")
      (description "ATMEGA328P-PU; 8 bit Microcontroller AVR 20MHz 1; 32kb Flash; 2kb RAM; I2C SPI 2")
      (fields (field (name "MANUFACTURER") "Microchip / Atmel"))
      (libsource (lib "Component Schematic Library V1") (part "ATMEGA328P-PU_Microcontroller"))
    )
    (comp (ref "U3")
      (value "SN74AHC1G09DBVR")
      (footprint "DBV SOT 23_5")
      (description "Single 2-input, 2-V to 5.5-V AND gate with open-drain outputs 5-SOT-23 -55 to 125")
      (fields (field (name "MANUFACTURER") "Texas Instruments"))
      (libsource (lib "Component Schematic Library V1") (part "AND_Gate 2input"))
    )
    (comp (ref "U4")
      (value "TL1963A-33DCQR")
      (footprint "DCQR_PDSO_G6")
      (description "LDO Regulator Pos 3.3V 1.5A 6-Pin(5+Tab) SOT-223 T/R")
      (fields (field (name "MANUFACTURER") "Texas Instruments"))
      (libsource (lib "Component Schematic Library V1") (part "3V3 Regulator"))
    )
    (comp (ref "U5")
      (value "SN74AHC1G09DBVR")
      (footprint "DBV SOT 23_5")
      (description "Single 2-input, 2-V to 5.5-V AND gate with open-drain outputs 5-SOT-23 -55 to 125")
      (fields (field (name "MANUFACTURER") "Texas Instruments"))
      (libsource (lib "Component Schematic Library V1") (part "AND_Gate 2input"))
    )
    (comp (ref "U6")
      (value "SN74AHC1G09DBVR")
      (footprint "DBV SOT 23_5")
      (description "Single 2-input, 2-V to 5.5-V AND gate with open-drain outputs 5-SOT-23 -55 to 125")
      (fields (field (name "MANUFACTURER") "Texas Instruments"))
      (libsource (lib "Component Schematic Library V1") (part "AND_Gate 2input"))
    )
    (comp (ref "U7")
      (value "SN74AHC1G09DBVR")
      (footprint "DBV SOT 23_5")
      (description "Single 2-input, 2-V to 5.5-V AND gate with open-drain outputs 5-SOT-23 -55 to 125")
      (fields (field (name "MANUFACTURER") "Texas Instruments"))
      (libsource (lib "Component Schematic Library V1") (part "AND_Gate 2input"))
    )
    (comp (ref "y1")
      (value "ECS-160-20-23A-EN-TR")
      (footprint "Xtal_16MHZ")
      (description "Crystal 16MHz ±30ppm (Tol) ±50ppm (Stability) 20pF FUND 60Ohm 2-Pin Mini-CSMD T/R")
      (fields (field (name "MANUFACTURER") "ECS International") (field (name "TOLERANCE") "30ppm"))
      (libsource (lib "Component Schematic Library V1") (part "Xtal_16_MHZ"))
    )
    (comp (ref "y2")
      (value "ECS-160-20-23A-EN-TR")
      (footprint "Xtal_16MHZ")
      (description "Crystal 16MHz ±30ppm (Tol) ±50ppm (Stability) 20pF FUND 60Ohm 2-Pin Mini-CSMD T/R")
      (fields (field (name "MANUFACTURER") "ECS International") (field (name "TOLERANCE") "30ppm"))
      (libsource (lib "Component Schematic Library V1") (part "Xtal_16_MHZ"))
    )
    (comp (ref "Z1")
      (value "CG0603MLC-05E")
      (footprint "R0603")
      (description "ESD Suppressor Multilayer Varistor 5V Automotive 2-Pin Case 0603(1608Metric) T/R")
      (fields (field (name "MANUFACTURER") "Bourns") (field (name "VOLTAGE") "5V"))
      (libsource (lib "Component Schematic Library V1") (part "Varistor"))
    )
    (comp (ref "Z2")
      (value "CG0603MLC-05E")
      (footprint "R0603")
      (description "ESD Suppressor Multilayer Varistor 5V Automotive 2-Pin Case 0603(1608Metric) T/R")
      (fields (field (name "MANUFACTURER") "Bourns") (field (name "VOLTAGE") "5V"))
      (libsource (lib "Component Schematic Library V1") (part "Varistor"))
    )
  )
  (nets
    (net (code "1") (name "+3V3") (class "Default")
      (node (ref "C15") (pin "2") (pinfunction "2_2") (pintype "passive"))
      (node (ref "C26") (pin "1") (pinfunction "1_1") (pintype "passive"))
      (node (ref "J6") (pin "4") (pinfunction "4_4") (pintype "passive"))
      (node (ref "JP3") (pin "3") (pinfunction "3_3") (pintype "passive"))
      (node (ref "R20") (pin "2") (pinfunction "3_2") (pintype "passive"))
      (node (ref "U4") (pin "4") (pinfunction "OUT_4") (pintype "passive"))
      (node (ref "U4") (pin "5") (pinfunction "SENSE_5") (pintype "passive"))
    )
    (net (code "2") (name "+5V") (class "Default")
      (node (ref "C17") (pin "2") (pinfunction "2_2") (pintype "passive"))
      (node (ref "C2") (pin "1") (pinfunction "1_1") (pintype "passive"))
      (node (ref "C25") (pin "1") (pinfunction "1_1") (pintype "passive"))
      (node (ref "C7") (pin "1") (pinfunction "1_1") (pintype "passive"))
      (node (ref "J6") (pin "5") (pinfunction "5_5") (pintype "passive"))
      (node (ref "J7") (pin "1") (pinfunction "1_1") (pintype "passive"))
      (node (ref "JP3") (pin "1") (pinfunction "1_1") (pintype "passive"))
      (node (ref "L1") (pin "2") (pinfunction "2_2") (pintype "passive"))
      (node (ref "R19") (pin "1") (pinfunction "2_1") (pintype "passive"))
      (node (ref "U1") (pin "31") (pinfunction "UVCC_31") (pintype "passive"))
      (node (ref "U4") (pin "1") (pinfunction "~{SHDN}_1") (pintype "passive"))
      (node (ref "U4") (pin "2") (pinfunction "IN_2") (pintype "passive"))
    )
    (net (code "3") (name "+5{slash}3V3") (class "Default")
      (node (ref "C13") (pin "2") (pinfunction "2_2") (pintype "passive"))
      (node (ref "C14") (pin "2") (pinfunction "2_2") (pintype "passive"))
      (node (ref "C16") (pin "1") (pinfunction "1_1") (pintype "passive"))
      (node (ref "C27") (pin "2") (pinfunction "2_2") (pintype "passive"))
      (node (ref "C28") (pin "2") (pinfunction "2_2") (pintype "passive"))
      (node (ref "C29") (pin "2") (pinfunction "2_2") (pintype "passive"))
      (node (ref "C6") (pin "2") (pinfunction "2_2") (pintype "passive"))
      (node (ref "D5") (pin "1") (pinfunction "Cathode_1") (pintype "passive"))
      (node (ref "D6") (pin "1") (pinfunction "Cathode_1") (pintype "passive"))
      (node (ref "FB1") (pin "1") (pinfunction "1_1") (pintype "passive"))
      (node (ref "FB2") (pin "1") (pinfunction "1_1") (pintype "passive"))
      (node (ref "FB3") (pin "1") (pinfunction "1_1") (pintype "passive"))
      (node (ref "J3") (pin "6") (pinfunction "6_6") (pintype "passive"))
      (node (ref "J4") (pin "6") (pinfunction "6_6") (pintype "passive"))
      (node (ref "J6") (pin "2") (pinfunction "2_2") (pintype "passive"))
      (node (ref "JP3") (pin "2") (pinfunction "2_2") (pintype "passive"))
      (node (ref "R1") (pin "2") (pinfunction "3_2") (pintype "passive"))
      (node (ref "R13") (pin "1") (pinfunction "2_1") (pintype "passive"))
      (node (ref "R14") (pin "1") (pinfunction "2_1") (pintype "passive"))
      (node (ref "R15") (pin "1") (pinfunction "2_1") (pintype "passive"))
      (node (ref "R17") (pin "2") (pinfunction "3_2") (pintype "passive"))
      (node (ref "R18") (pin "2") (pinfunction "3_2") (pintype "passive"))
      (node (ref "R19") (pin "2") (pinfunction "3_2") (pintype "passive"))
      (node (ref "R20") (pin "1") (pinfunction "2_1") (pintype "passive"))
      (node (ref "R21") (pin "1") (pinfunction "2_1") (pintype "passive"))
      (node (ref "R22") (pin "2") (pinfunction "3_2") (pintype "passive"))
      (node (ref "R23") (pin "2") (pinfunction "3_2") (pintype "passive"))
      (node (ref "R24") (pin "2") (pinfunction "3_2") (pintype "passive"))
      (node (ref "R7") (pin "2") (pinfunction "3_2") (pintype "passive"))
      (node (ref "U3") (pin "5") (pinfunction "6_5") (pintype "passive"))
      (node (ref "U5") (pin "5") (pinfunction "6_5") (pintype "passive"))
      (node (ref "U6") (pin "5") (pinfunction "6_5") (pintype "passive"))
      (node (ref "U7") (pin "5") (pinfunction "6_5") (pintype "passive"))
    )
    (net (code "4") (name "+AREF") (class "Default")
      (node (ref "C12") (pin "1") (pinfunction "1_1") (pintype "passive"))
      (node (ref "C22") (pin "2") (pinfunction "2_2") (pintype "passive"))
      (node (ref "J5") (pin "8") (pinfunction "8_8") (pintype "passive"))
      (node (ref "U2") (pin "21") (pinfunction "AREF_21") (pintype "passive"))
    )
    (net (code "5") (name "/3V3_16U2_UCAP") (class "Default")
      (node (ref "C8") (pin "2") (pinfunction "2_2") (pintype "passive"))
      (node (ref "R3") (pin "1") (pinfunction "2_1") (pintype "passive"))
      (node (ref "U1") (pin "27") (pinfunction "UCAP_27") (pintype "passive"))
    )
    (net (code "6") (name "/16U2 PROG 328P RESETn") (class "Default")
      (node (ref "JP2") (pin "2") (pinfunction "2_2") (pintype "passive"))
      (node (ref "R7") (pin "1") (pinfunction "2_1") (pintype "passive"))
      (node (ref "U1") (pin "13") (pinfunction "(CTS/HWB/AIN6/TO/INT7)PD7_13") (pintype "passive"))
    )
    (net (code "7") (name "/16U2_ RSTn") (class "Default")
      (node (ref "JP1") (pin "4") (pinfunction "4_4") (pintype "passive"))
      (node (ref "R1") (pin "1") (pinfunction "2_1") (pintype "passive"))
      (node (ref "U1") (pin "24") (pinfunction "~{RESET}(PC1/DW)_24") (pintype "passive"))
      (node (ref "U5") (pin "4") (pinfunction "5_4") (pintype "passive"))
    )
    (net (code "8") (name "/16U2_16MHZ_XTAL_1") (class "Default")
      (node (ref "C11") (pin "2") (pinfunction "2_2") (pintype "passive"))
      (node (ref "R9") (pin "1") (pinfunction "2_1") (pintype "passive"))
      (node (ref "U1") (pin "1") (pinfunction "XTAL1_1") (pintype "passive"))
      (node (ref "y1") (pin "1") (pinfunction "2_1") (pintype "passive"))
    )
    (net (code "9") (name "/16U2_16MHZ_XTAL_2") (class "Default")
      (node (ref "C10") (pin "2") (pinfunction "2_2") (pintype "passive"))
      (node (ref "R9") (pin "2") (pinfunction "3_2") (pintype "passive"))
      (node (ref "U1") (pin "2") (pinfunction "XTAL2(PC0)_2") (pintype "passive"))
      (node (ref "y1") (pin "2") (pinfunction "2_2") (pintype "passive"))
    )
    (net (code "10") (name "/16U2_HDR_RST") (class "Default")
      (node (ref "J3") (pin "3") (pinfunction "3_3") (pintype "passive"))
      (node (ref "JP1") (pin "3") (pinfunction "3_3") (pintype "passive"))
    )
    (net (code "11") (name "/16U2_MISO") (class "Default")
      (node (ref "J3") (pin "1") (pinfunction "1_1") (pintype "passive"))
      (node (ref "U1") (pin "17") (pinfunction "(PD0/MISO/PCINT3)PB3_17") (pintype "passive"))
    )
    (net (code "12") (name "/16U2_MOSI") (class "Default")
      (node (ref "J3") (pin "5") (pinfunction "5_5") (pintype "passive"))
      (node (ref "U1") (pin "16") (pinfunction "(PDI/MOSI/PCINT2)PB2_16") (pintype "passive"))
    )
    (net (code "13") (name "/16U2_PB4") (class "Default")
      (node (ref "J1") (pin "2") (pinfunction "2_2") (pintype "passive"))
      (node (ref "JP1") (pin "2") (pinfunction "2_2") (pintype "passive"))
      (node (ref "U1") (pin "18") (pinfunction "(T1/PCINT4)PB4_18") (pintype "passive"))
    )
    (net (code "14") (name "/16U2_PB5") (class "Default")
      (node (ref "J1") (pin "1") (pinfunction "1_1") (pintype "passive"))
      (node (ref "U1") (pin "19") (pinfunction "(PCINT5)PB5_19") (pintype "passive"))
    )
    (net (code "15") (name "/16U2_PB6") (class "Default")
      (node (ref "J1") (pin "3") (pinfunction "3_3") (pintype "passive"))
      (node (ref "U1") (pin "20") (pinfunction "(PCINT6)PB6_20") (pintype "passive"))
    )
    (net (code "16") (name "/16U2_PB7") (class "Default")
      (node (ref "J1") (pin "4") (pinfunction "4_4") (pintype "passive"))
      (node (ref "U1") (pin "21") (pinfunction "(PCINT7/OC0A/OC1C)PB7_21") (pintype "passive"))
    )
    (net (code "17") (name "/16U2_SCLK") (class "Default")
      (node (ref "J3") (pin "2") (pinfunction "2_2") (pintype "passive"))
      (node (ref "R6") (pin "2") (pinfunction "3_2") (pintype "passive"))
    )
    (net (code "18") (name "/328P RSTn") (class "Default")
      (node (ref "J4") (pin "3") (pinfunction "3_3") (pintype "passive"))
      (node (ref "J6") (pin "3") (pinfunction "3_3") (pintype "passive"))
      (node (ref "JP1") (pin "1") (pinfunction "1_1") (pintype "passive"))
      (node (ref "R13") (pin "2") (pinfunction "3_2") (pintype "passive"))
      (node (ref "U2") (pin "1") (pinfunction "PC6(PCINT14/~{RESET})_1") (pintype "passive"))
      (node (ref "U7") (pin "4") (pinfunction "5_4") (pintype "passive"))
    )
    (net (code "19") (name "/328P_16MHZ_XTAL_1") (class "Default")
      (node (ref "C24") (pin "2") (pinfunction "2_2") (pintype "passive"))
      (node (ref "R16") (pin "1") (pinfunction "2_1") (pintype "passive"))
      (node (ref "U2") (pin "9") (pinfunction "(PCINT6/XTAL1/TOSC1)_PB6_9") (pintype "passive"))
      (node (ref "y2") (pin "1") (pinfunction "2_1") (pintype "passive"))
    )
    (net (code "20") (name "/328P_16MHZ_XTAL_2") (class "Default")
      (node (ref "C23") (pin "2") (pinfunction "2_2") (pintype "passive"))
      (node (ref "R16") (pin "2") (pinfunction "3_2") (pintype "passive"))
      (node (ref "U2") (pin "10") (pinfunction "(PCINT7/XTAL2/TOSC2)_PB7_10") (pintype "passive"))
      (node (ref "y2") (pin "2") (pinfunction "2_2") (pintype "passive"))
    )
    (net (code "21") (name "/328P_AUTO_RSTn") (class "Default")
      (node (ref "C9") (pin "1") (pinfunction "1_1") (pintype "passive"))
      (node (ref "R21") (pin "2") (pinfunction "3_2") (pintype "passive"))
      (node (ref "U7") (pin "1") (pinfunction "2_1") (pintype "passive"))
    )
    (net (code "22") (name "/AD0") (class "Default")
      (node (ref "J9") (pin "1") (pinfunction "1_1") (pintype "passive"))
      (node (ref "U2") (pin "23") (pinfunction "PC0_(ADC0/PCINT8)_23") (pintype "passive"))
    )
    (net (code "23") (name "/AD1") (class "Default")
      (node (ref "J9") (pin "2") (pinfunction "2_2") (pintype "passive"))
      (node (ref "U2") (pin "24") (pinfunction "PC1_(ADC1/PCINT9)_24") (pintype "passive"))
    )
    (net (code "24") (name "/AD2") (class "Default")
      (node (ref "J9") (pin "3") (pinfunction "3_3") (pintype "passive"))
      (node (ref "U2") (pin "25") (pinfunction "PC2_(ADC2/PCINT10)_25") (pintype "passive"))
    )
    (net (code "25") (name "/AD3") (class "Default")
      (node (ref "J9") (pin "4") (pinfunction "4_4") (pintype "passive"))
      (node (ref "U2") (pin "26") (pinfunction "PC3_(ADC3/PCINT11)_26") (pintype "passive"))
    )
    (net (code "26") (name "/AD4{slash}SDA") (class "Default")
      (node (ref "J5") (pin "9") (pinfunction "9_9") (pintype "passive"))
      (node (ref "J9") (pin "5") (pinfunction "5_5") (pintype "passive"))
      (node (ref "U2") (pin "27") (pinfunction "PC4_(ADC4/SDA/PCINT12)_27") (pintype "passive"))
    )
    (net (code "27") (name "/AD5{slash}SCL") (class "Default")
      (node (ref "J5") (pin "10") (pinfunction "10_10") (pintype "passive"))
      (node (ref "J9") (pin "6") (pinfunction "6_6") (pintype "passive"))
      (node (ref "U2") (pin "28") (pinfunction "PC5_(ADC5/SCL/PCINT13)_28") (pintype "passive"))
    )
    (net (code "28") (name "/I08") (class "Default")
      (node (ref "J5") (pin "1") (pinfunction "1_1") (pintype "passive"))
      (node (ref "R25") (pin "2") (pinfunction "3_2") (pintype "passive"))
      (node (ref "U2") (pin "14") (pinfunction "(PCINT0/CLKO/ICP1)_PB0_14") (pintype "passive"))
    )
    (net (code "29") (name "/I09") (class "Default")
      (node (ref "J5") (pin "2") (pinfunction "2_2") (pintype "passive"))
      (node (ref "U2") (pin "15") (pinfunction "PB1_(OC1A/PCINT1)_15") (pintype "passive"))
    )
    (net (code "30") (name "/IO0") (class "Default")
      (node (ref "J10") (pin "1") (pinfunction "1_1") (pintype "passive"))
      (node (ref "R10") (pin "2") (pinfunction "3_2") (pintype "passive"))
      (node (ref "U2") (pin "2") (pinfunction "(PCINT16/RXD)_PD0_2") (pintype "passive"))
    )
    (net (code "31") (name "/IO1") (class "Default")
      (node (ref "J10") (pin "2") (pinfunction "2_2") (pintype "passive"))
      (node (ref "R11") (pin "2") (pinfunction "3_2") (pintype "passive"))
      (node (ref "U2") (pin "3") (pinfunction "(PCINT17/TXD)_PD1_3") (pintype "passive"))
    )
    (net (code "32") (name "/IO2") (class "Default")
      (node (ref "J10") (pin "3") (pinfunction "3_3") (pintype "passive"))
      (node (ref "U2") (pin "4") (pinfunction "(PCINT18/INT0)_PD2_4") (pintype "passive"))
    )
    (net (code "33") (name "/IO3") (class "Default")
      (node (ref "J10") (pin "4") (pinfunction "4_4") (pintype "passive"))
      (node (ref "U2") (pin "5") (pinfunction "(PCINT19/OC2B/INT1)_PD3_5") (pintype "passive"))
    )
    (net (code "34") (name "/IO4") (class "Default")
      (node (ref "J10") (pin "5") (pinfunction "5_5") (pintype "passive"))
      (node (ref "U2") (pin "6") (pinfunction "(PCINT20/XCK/T0)_PD4_6") (pintype "passive"))
    )
    (net (code "35") (name "/IO5") (class "Default")
      (node (ref "J10") (pin "6") (pinfunction "6_6") (pintype "passive"))
      (node (ref "U2") (pin "11") (pinfunction "(PCINT21/OC0B/T1)_PD5_11") (pintype "passive"))
    )
    (net (code "36") (name "/IO6") (class "Default")
      (node (ref "J10") (pin "7") (pinfunction "7_7") (pintype "passive"))
      (node (ref "U2") (pin "12") (pinfunction "(PCINT22/OC0A/AIN0)_PD6_12") (pintype "passive"))
    )
    (net (code "37") (name "/IO7") (class "Default")
      (node (ref "J10") (pin "8") (pinfunction "8_8") (pintype "passive"))
      (node (ref "U2") (pin "13") (pinfunction "(PCINT23/AIN1)_PD7_13") (pintype "passive"))
    )
    (net (code "38") (name "/MISO") (class "Default")
      (node (ref "J4") (pin "1") (pinfunction "1_1") (pintype "passive"))
      (node (ref "J5") (pin "5") (pinfunction "5_5") (pintype "passive"))
      (node (ref "U2") (pin "18") (pinfunction "PB4_(MISO/PCINT4)_18") (pintype "passive"))
    )
    (net (code "39") (name "/MOSI") (class "Default")
      (node (ref "J4") (pin "5") (pinfunction "5_5") (pintype "passive"))
      (node (ref "J5") (pin "4") (pinfunction "4_4") (pintype "passive"))
      (node (ref "U2") (pin "17") (pinfunction "PB3_(MOSI/OC2A/PCINT3)_17") (pintype "passive"))
    )
    (net (code "40") (name "/RX_LED") (class "Default")
      (node (ref "D2") (pin "1") (pinfunction "Cathode_1") (pintype "passive"))
      (node (ref "U1") (pin "10") (pinfunction "(INT5/AIN3)PD4_10") (pintype "passive"))
    )
    (net (code "41") (name "/SCK") (class "Default")
      (node (ref "J4") (pin "2") (pinfunction "2_2") (pintype "passive"))
      (node (ref "J5") (pin "6") (pinfunction "6_6") (pintype "passive"))
      (node (ref "R12") (pin "2") (pinfunction "3_2") (pintype "passive"))
      (node (ref "U3") (pin "1") (pinfunction "2_1") (pintype "passive"))
      (node (ref "U3") (pin "2") (pinfunction "3_2") (pintype "passive"))
    )
    (net (code "42") (name "/SCK_R") (class "Default")
      (node (ref "R12") (pin "1") (pinfunction "2_1") (pintype "passive"))
      (node (ref "U2") (pin "19") (pinfunction "PB5_(SCK/PCINT5)_19") (pintype "passive"))
    )
    (net (code "43") (name "/SS") (class "Default")
      (node (ref "J5") (pin "3") (pinfunction "3_3") (pintype "passive"))
      (node (ref "U2") (pin "16") (pinfunction "PB2_(SS/OC1B/PCINT2)_16") (pintype "passive"))
    )
    (net (code "44") (name "/TX_LED") (class "Default")
      (node (ref "D1") (pin "1") (pinfunction "Cathode_1") (pintype "passive"))
      (node (ref "U1") (pin "11") (pinfunction "(XCK/AIN4/PCINT12)PD5_11") (pintype "passive"))
    )
    (net (code "45") (name "GND") (class "Default")
      (node (ref "C1") (pin "2") (pinfunction "2_2") (pintype "passive"))
      (node (ref "C10") (pin "1") (pinfunction "1_1") (pintype "passive"))
      (node (ref "C11") (pin "1") (pinfunction "1_1") (pintype "passive"))
      (node (ref "C12") (pin "2") (pinfunction "2_2") (pintype "passive"))
      (node (ref "C13") (pin "1") (pinfunction "1_1") (pintype "passive"))
      (node (ref "C14") (pin "1") (pinfunction "1_1") (pintype "passive"))
      (node (ref "C15") (pin "1") (pinfunction "1_1") (pintype "passive"))
      (node (ref "C16") (pin "2") (pinfunction "2_2") (pintype "passive"))
      (node (ref "C17") (pin "1") (pinfunction "1_1") (pintype "passive"))
      (node (ref "C18") (pin "2") (pinfunction "2_2") (pintype "passive"))
      (node (ref "C19") (pin "1") (pinfunction "1_1") (pintype "passive"))
      (node (ref "C2") (pin "2") (pinfunction "2_2") (pintype "passive"))
      (node (ref "C20") (pin "2") (pinfunction "2_2") (pintype "passive"))
      (node (ref "C21") (pin "1") (pinfunction "1_1") (pintype "passive"))
      (node (ref "C22") (pin "1") (pinfunction "1_1") (pintype "passive"))
      (node (ref "C23") (pin "1") (pinfunction "1_1") (pintype "passive"))
      (node (ref "C24") (pin "1") (pinfunction "1_1") (pintype "passive"))
      (node (ref "C25") (pin "2") (pinfunction "2_2") (pintype "passive"))
      (node (ref "C26") (pin "2") (pinfunction "2_2") (pintype "passive"))
      (node (ref "C27") (pin "1") (pinfunction "1_1") (pintype "passive"))
      (node (ref "C28") (pin "1") (pinfunction "1_1") (pintype "passive"))
      (node (ref "C29") (pin "1") (pinfunction "1_1") (pintype "passive"))
      (node (ref "C3") (pin "2") (pinfunction "2_2") (pintype "passive"))
      (node (ref "C30") (pin "1") (pinfunction "1_1") (pintype "passive"))
      (node (ref "C31") (pin "1") (pinfunction "1_1") (pintype "passive"))
      (node (ref "C32") (pin "1") (pinfunction "1_1") (pintype "passive"))
      (node (ref "C4") (pin "1") (pinfunction "1_1") (pintype "passive"))
      (node (ref "C5") (pin "2") (pinfunction "2_2") (pintype "passive"))
      (node (ref "C6") (pin "1") (pinfunction "1_1") (pintype "passive"))
      (node (ref "C7") (pin "2") (pinfunction "2_2") (pintype "passive"))
      (node (ref "C8") (pin "1") (pinfunction "1_1") (pintype "passive"))
      (node (ref "D4") (pin "1") (pinfunction "Cathode_1") (pintype "passive"))
      (node (ref "J2") (pin "10") (pinfunction "10_10") (pintype "passive"))
      (node (ref "J2") (pin "11") (pinfunction "11_11") (pintype "passive"))
      (node (ref "J2") (pin "5") (pinfunction "5_5") (pintype "passive"))
      (node (ref "J2") (pin "6") (pinfunction "6_6") (pintype "passive"))
      (node (ref "J2") (pin "7") (pinfunction "7_7") (pintype "passive"))
      (node (ref "J2") (pin "8") (pinfunction "8_8") (pintype "passive"))
      (node (ref "J2") (pin "9") (pinfunction "9_9") (pintype "passive"))
      (node (ref "J3") (pin "4") (pinfunction "4_4") (pintype "passive"))
      (node (ref "J4") (pin "4") (pinfunction "4_4") (pintype "passive"))
      (node (ref "J5") (pin "7") (pinfunction "7_7") (pintype "passive"))
      (node (ref "J6") (pin "6") (pinfunction "6_6") (pintype "passive"))
      (node (ref "J6") (pin "7") (pinfunction "7_7") (pintype "passive"))
      (node (ref "J8") (pin "1") (pinfunction "1_1") (pintype "passive"))
      (node (ref "MH1") (pin "1") (pinfunction "1_1") (pintype "passive"))
      (node (ref "MH2") (pin "1") (pinfunction "1_1") (pintype "passive"))
      (node (ref "MH3") (pin "1") (pinfunction "1_1") (pintype "passive"))
      (node (ref "R5") (pin "1") (pinfunction "2_1") (pintype "passive"))
      (node (ref "R8") (pin "1") (pinfunction "2_1") (pintype "passive"))
      (node (ref "SW1") (pin "1") (pinfunction "1_1") (pintype "passive"))
      (node (ref "SW1") (pin "2") (pinfunction "2_2") (pintype "passive"))
      (node (ref "SW2") (pin "1") (pinfunction "1_1") (pintype "passive"))
      (node (ref "SW2") (pin "2") (pinfunction "2_2") (pintype "passive"))
      (node (ref "U1") (pin "28") (pinfunction "UGND_28") (pintype "passive"))
      (node (ref "U1") (pin "3") (pinfunction "GND_3") (pintype "passive"))
      (node (ref "U2") (pin "22") (pinfunction "GND2_22") (pintype "passive"))
      (node (ref "U2") (pin "8") (pinfunction "GND1_8") (pintype "passive"))
      (node (ref "U3") (pin "3") (pinfunction "4_3") (pintype "passive"))
      (node (ref "U4") (pin "3") (pinfunction "GND_3") (pintype "passive"))
      (node (ref "U4") (pin "6") (pinfunction "GND/EPAD_6") (pintype "passive"))
      (node (ref "Z1") (pin "2") (pinfunction "2_2") (pintype "passive"))
      (node (ref "Z2") (pin "2") (pinfunction "2_2") (pintype "passive"))
    )
    (net (code "46") (name "Net-(C1-Pad1)") (class "Default")
      (node (ref "C1") (pin "1") (pinfunction "1_1") (pintype "passive"))
      (node (ref "J2") (pin "1") (pinfunction "1_1") (pintype "passive"))
      (node (ref "L1") (pin "1") (pinfunction "1_1") (pintype "passive"))
    )
    (net (code "47") (name "Net-(C9-Pad2)") (class "Default")
      (node (ref "C9") (pin "2") (pinfunction "2_2") (pintype "passive"))
      (node (ref "JP2") (pin "1") (pinfunction "1_1") (pintype "passive"))
    )
    (net (code "48") (name "Net-(D1-Anode)") (class "Default")
      (node (ref "D1") (pin "2") (pinfunction "Anode_2") (pintype "passive"))
      (node (ref "R14") (pin "2") (pinfunction "3_2") (pintype "passive"))
    )
    (net (code "49") (name "Net-(D2-Anode)") (class "Default")
      (node (ref "D2") (pin "2") (pinfunction "Anode_2") (pintype "passive"))
      (node (ref "R15") (pin "2") (pinfunction "3_2") (pintype "passive"))
    )
    (net (code "50") (name "Net-(D3-Anode)") (class "Default")
      (node (ref "D3") (pin "2") (pinfunction "Anode_2") (pintype "passive"))
      (node (ref "R17") (pin "1") (pinfunction "2_1") (pintype "passive"))
    )
    (net (code "51") (name "Net-(D3-Cathode)") (class "Default")
      (node (ref "D3") (pin "1") (pinfunction "Cathode_1") (pintype "passive"))
      (node (ref "U3") (pin "4") (pinfunction "5_4") (pintype "passive"))
    )
    (net (code "52") (name "Net-(D4-Anode)") (class "Default")
      (node (ref "D4") (pin "2") (pinfunction "Anode_2") (pintype "passive"))
      (node (ref "R18") (pin "1") (pinfunction "2_1") (pintype "passive"))
    )
    (net (code "53") (name "Net-(D5-Anode)") (class "Default")
      (node (ref "D5") (pin "2") (pinfunction "Anode_2") (pintype "passive"))
      (node (ref "R22") (pin "1") (pinfunction "2_1") (pintype "passive"))
      (node (ref "R26") (pin "1") (pinfunction "2_1") (pintype "passive"))
    )
    (net (code "54") (name "Net-(D6-Anode)") (class "Default")
      (node (ref "D6") (pin "2") (pinfunction "Anode_2") (pintype "passive"))
      (node (ref "R24") (pin "1") (pinfunction "2_1") (pintype "passive"))
      (node (ref "R28") (pin "1") (pinfunction "2_1") (pintype "passive"))
      (node (ref "SW2") (pin "3") (pinfunction "3_3") (pintype "passive"))
      (node (ref "SW2") (pin "4") (pinfunction "4_4") (pintype "passive"))
    )
    (net (code "55") (name "Net-(R2-2)") (class "Default")
      (node (ref "J2") (pin "2") (pinfunction "2_2") (pintype "passive"))
      (node (ref "R2") (pin "1") (pinfunction "2_1") (pintype "passive"))
      (node (ref "Z1") (pin "1") (pinfunction "1_1") (pintype "passive"))
    )
    (net (code "56") (name "Net-(R2-3)") (class "Default")
      (node (ref "R2") (pin "2") (pinfunction "3_2") (pintype "passive"))
      (node (ref "U1") (pin "30") (pinfunction "D-_30") (pintype "passive"))
    )
    (net (code "57") (name "Net-(R3-3)") (class "Default")
      (node (ref "C3") (pin "1") (pinfunction "1_1") (pintype "passive"))
      (node (ref "C4") (pin "2") (pinfunction "2_2") (pintype "passive"))
      (node (ref "C5") (pin "1") (pinfunction "1_1") (pintype "passive"))
      (node (ref "FB1") (pin "2") (pinfunction "2_2") (pintype "passive"))
      (node (ref "R3") (pin "2") (pinfunction "3_2") (pintype "passive"))
      (node (ref "U1") (pin "32") (pinfunction "AVCC_32") (pintype "passive"))
      (node (ref "U1") (pin "4") (pinfunction "VCC_4") (pintype "passive"))
    )
    (net (code "58") (name "Net-(R4-2)") (class "Default")
      (node (ref "J2") (pin "3") (pinfunction "3_3") (pintype "passive"))
      (node (ref "R4") (pin "1") (pinfunction "2_1") (pintype "passive"))
      (node (ref "Z2") (pin "1") (pinfunction "1_1") (pintype "passive"))
    )
    (net (code "59") (name "Net-(R4-3)") (class "Default")
      (node (ref "R4") (pin "2") (pinfunction "3_2") (pintype "passive"))
      (node (ref "U1") (pin "29") (pinfunction "D+_29") (pintype "passive"))
    )
    (net (code "60") (name "Net-(R5-3)") (class "Default")
      (node (ref "J2") (pin "4") (pinfunction "4_4") (pintype "passive"))
      (node (ref "R5") (pin "2") (pinfunction "3_2") (pintype "passive"))
    )
    (net (code "61") (name "Net-(R6-2)") (class "Default")
      (node (ref "R6") (pin "1") (pinfunction "2_1") (pintype "passive"))
      (node (ref "U1") (pin "15") (pinfunction "(SCLK/PCINT1)PB1_15") (pintype "passive"))
    )
    (net (code "62") (name "Net-(R8-3)") (class "Default")
      (node (ref "JP2") (pin "3") (pinfunction "3_3") (pintype "passive"))
      (node (ref "R8") (pin "2") (pinfunction "3_2") (pintype "passive"))
    )
    (net (code "63") (name "Net-(R10-2)") (class "Default")
      (node (ref "R10") (pin "1") (pinfunction "2_1") (pintype "passive"))
      (node (ref "U1") (pin "9") (pinfunction "(TXD1/INT3)PD3_9") (pintype "passive"))
    )
    (net (code "64") (name "Net-(R11-2)") (class "Default")
      (node (ref "R11") (pin "1") (pinfunction "2_1") (pintype "passive"))
      (node (ref "U1") (pin "8") (pinfunction "(RXD1/AIN1/INT2)PD2_8") (pintype "passive"))
    )
    (net (code "65") (name "Net-(R23-2)") (class "Default")
      (node (ref "R23") (pin "1") (pinfunction "2_1") (pintype "passive"))
      (node (ref "R27") (pin "1") (pinfunction "2_1") (pintype "passive"))
      (node (ref "SW1") (pin "3") (pinfunction "3_3") (pintype "passive"))
      (node (ref "SW1") (pin "4") (pinfunction "4_4") (pintype "passive"))
    )
    (net (code "66") (name "Net-(R25-2)") (class "Default")
      (node (ref "R25") (pin "1") (pinfunction "2_1") (pintype "passive"))
      (node (ref "U6") (pin "4") (pinfunction "5_4") (pintype "passive"))
    )
    (net (code "67") (name "Net-(R26-3)") (class "Default")
      (node (ref "C30") (pin "2") (pinfunction "2_2") (pintype "passive"))
      (node (ref "R26") (pin "2") (pinfunction "3_2") (pintype "passive"))
      (node (ref "U5") (pin "1") (pinfunction "2_1") (pintype "passive"))
      (node (ref "U5") (pin "2") (pinfunction "3_2") (pintype "passive"))
    )
    (net (code "68") (name "Net-(R27-3)") (class "Default")
      (node (ref "C31") (pin "2") (pinfunction "2_2") (pintype "passive"))
      (node (ref "R27") (pin "2") (pinfunction "3_2") (pintype "passive"))
      (node (ref "U6") (pin "1") (pinfunction "2_1") (pintype "passive"))
      (node (ref "U6") (pin "2") (pinfunction "3_2") (pintype "passive"))
    )
    (net (code "69") (name "Net-(R28-3)") (class "Default")
      (node (ref "C32") (pin "2") (pinfunction "2_2") (pintype "passive"))
      (node (ref "R28") (pin "2") (pinfunction "3_2") (pintype "passive"))
      (node (ref "U7") (pin "2") (pinfunction "3_2") (pintype "passive"))
    )
    (net (code "70") (name "Net-(U2-AVCC)") (class "Default")
      (node (ref "C20") (pin "1") (pinfunction "1_1") (pintype "passive"))
      (node (ref "C21") (pin "2") (pinfunction "2_2") (pintype "passive"))
      (node (ref "FB3") (pin "2") (pinfunction "2_2") (pintype "passive"))
      (node (ref "U2") (pin "20") (pinfunction "AVCC_20") (pintype "passive"))
    )
    (net (code "71") (name "Net-(U2-VCC)") (class "Default")
      (node (ref "C18") (pin "1") (pinfunction "1_1") (pintype "passive"))
      (node (ref "C19") (pin "2") (pinfunction "2_2") (pintype "passive"))
      (node (ref "FB2") (pin "2") (pinfunction "2_2") (pintype "passive"))
      (node (ref "U2") (pin "7") (pinfunction "VCC_7") (pintype "passive"))
    )
    (net (code "72") (name "unconnected-(J6-Pad1)") (class "Default")
      (node (ref "J6") (pin "1") (pinfunction "1_1") (pintype "passive+no_connect"))
    )
    (net (code "73") (name "unconnected-(J6-Pad8)") (class "Default")
      (node (ref "J6") (pin "8") (pinfunction "8_8") (pintype "passive+no_connect"))
    )
    (net (code "74") (name "unconnected-(MH4-Pad2)") (class "Default")
      (node (ref "MH4") (pin "2") (pinfunction "2_2") (pintype "passive"))
    )
    (net (code "75") (name "unconnected-(U1-(AIN0{slash}INT1)PD1-Pad7)") (class "Default")
      (node (ref "U1") (pin "7") (pinfunction "(AIN0/INT1)PD1_7") (pintype "passive+no_connect"))
    )
    (net (code "76") (name "unconnected-(U1-(AIN2{slash}PCINT11)PC2-Pad5)") (class "Default")
      (node (ref "U1") (pin "5") (pinfunction "(AIN2/PCINT11)PC2_5") (pintype "passive+no_connect"))
    )
    (net (code "77") (name "unconnected-(U1-(INT4{slash}ICP1{slash}CLK0)PC7-Pad22)") (class "Default")
      (node (ref "U1") (pin "22") (pinfunction "(INT4/ICP1/CLK0)PC7_22") (pintype "passive+no_connect"))
    )
    (net (code "78") (name "unconnected-(U1-(OC0B{slash}INT0)PD0-Pad6)") (class "Default")
      (node (ref "U1") (pin "6") (pinfunction "(OC0B/INT0)PD0_6") (pintype "passive+no_connect"))
    )
    (net (code "79") (name "unconnected-(U1-(OC1A{slash}PCINT8)PC6-Pad23)") (class "Default")
      (node (ref "U1") (pin "23") (pinfunction "(OC1A/PCINT8)PC6_23") (pintype "passive+no_connect"))
    )
    (net (code "80") (name "unconnected-(U1-(PCINT9{slash}OC1B)PC5-Pad25)") (class "Default")
      (node (ref "U1") (pin "25") (pinfunction "(PCINT9/OC1B)PC5_25") (pintype "passive+no_connect"))
    )
    (net (code "81") (name "unconnected-(U1-(PCINT10)PC4-Pad26)") (class "Default")
      (node (ref "U1") (pin "26") (pinfunction "(PCINT10)PC4_26") (pintype "passive+no_connect"))
    )
    (net (code "82") (name "unconnected-(U1-(RTS{slash}AIN5{slash}INT6)PD6-Pad12)") (class "Default")
      (node (ref "U1") (pin "12") (pinfunction "(RTS/AIN5/INT6)PD6_12") (pintype "passive+no_connect"))
    )
    (net (code "83") (name "unconnected-(U1-(SS{slash}PCINT0)PB0-Pad14)") (class "Default")
      (node (ref "U1") (pin "14") (pinfunction "(SS/PCINT0)PB0_14") (pintype "passive+no_connect"))
    )
    (net (code "84") (name "unconnected-(U5-4-Pad3)") (class "Default")
      (node (ref "U5") (pin "3") (pinfunction "4_3") (pintype "passive"))
    )
    (net (code "85") (name "unconnected-(U6-4-Pad3)") (class "Default")
      (node (ref "U6") (pin "3") (pinfunction "4_3") (pintype "passive"))
    )
    (net (code "86") (name "unconnected-(U7-4-Pad3)") (class "Default")
      (node (ref "U7") (pin "3") (pinfunction "4_3") (pintype "passive"))
    )
  )
)
